# single_board_voice_changer.net
KiCad netlist of a schematic drawn in EAGLE
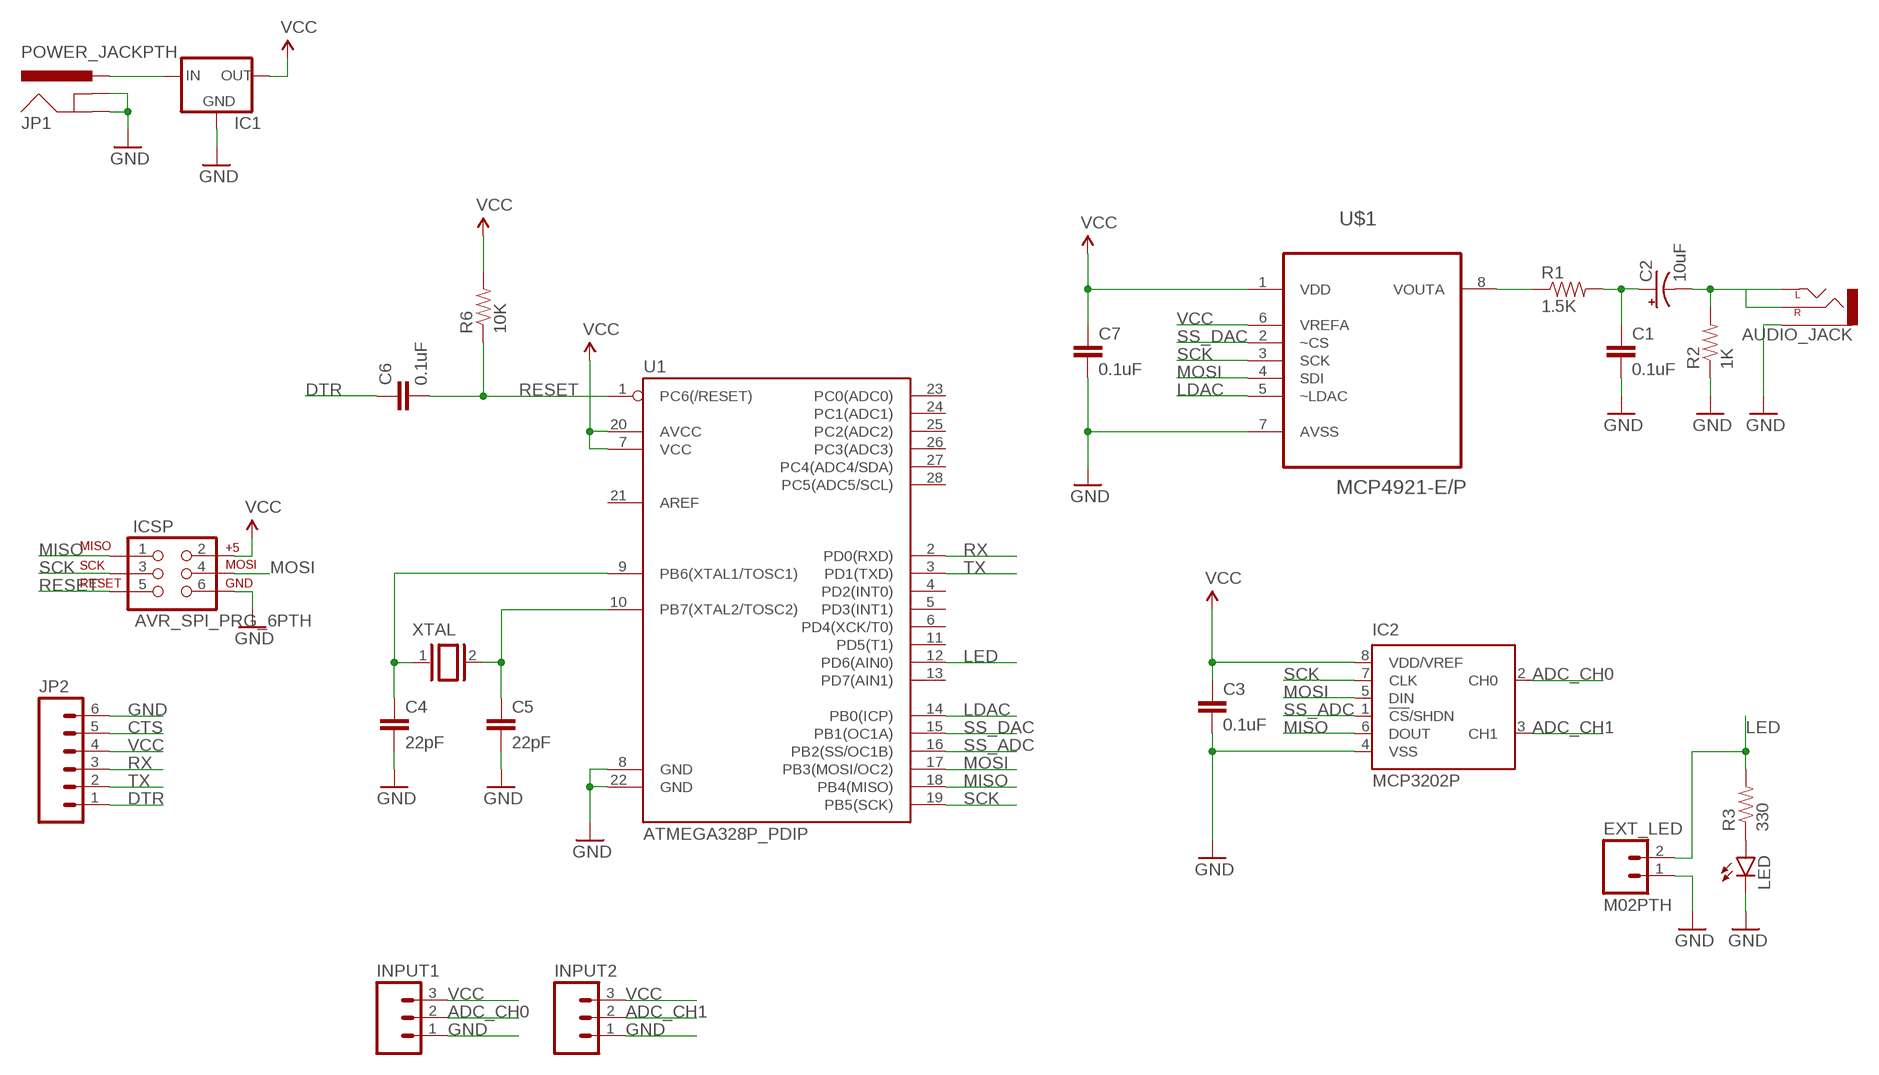
[diagram p0: schematic, sheet 1]

(export (version "E")
  (design (tool "Eeschema 10.0.6"))
  (components
    (comp (ref "AUDIO_JACK")
      (value "AUDIO-JACKPTH")
      (footprint "eagle-import:AUDIO-JACK")
      (libsource (lib "eagle-import") (part "AUDIO-JACKPTH"))
    )
    (comp (ref "C1")
      (value "0.1uF")
      (footprint "eagle-import:CAP-PTH-SMALL")
      (libsource (lib "eagle-import") (part "SparkFun-Passives_CAPPTH"))
    )
    (comp (ref "C2")
      (value "10uF")
      (footprint "eagle-import:CPOL-RADIAL-10UF-25V")
      (libsource (lib "eagle-import") (part "CAP_POLPTH2"))
    )
    (comp (ref "C3")
      (value "0.1uF")
      (footprint "eagle-import:CAP-PTH-SMALL")
      (libsource (lib "eagle-import") (part "SparkFun-Passives_CAPPTH"))
    )
    (comp (ref "C4")
      (value "22pF")
      (footprint "eagle-import:CAP-PTH-SMALL")
      (libsource (lib "eagle-import") (part "SparkFun-Passives_CAPPTH"))
    )
    (comp (ref "C5")
      (value "22pF")
      (footprint "eagle-import:CAP-PTH-SMALL")
      (libsource (lib "eagle-import") (part "SparkFun-Passives_CAPPTH"))
    )
    (comp (ref "C6")
      (value "0.1uF")
      (footprint "eagle-import:CAP-PTH-SMALL")
      (libsource (lib "eagle-import") (part "CAPPTH"))
    )
    (comp (ref "C7")
      (value "0.1uF")
      (footprint "eagle-import:CAP-PTH-SMALL")
      (libsource (lib "eagle-import") (part "SparkFun-Passives_CAPPTH"))
    )
    (comp (ref "EXT_LED")
      (value "M02PTH")
      (footprint "eagle-import:1X02")
      (libsource (lib "eagle-import") (part "M02PTH"))
    )
    (comp (ref "IC1")
      (value "V_REG_78XXSIDE")
      (footprint "eagle-import:78XXL")
      (libsource (lib "eagle-import") (part "V_REG_78XXSIDE"))
    )
    (comp (ref "IC2")
      (value "MCP3202P")
      (footprint "eagle-import:DIL8")
      (fields (field (name "MF") "MICROCHIP") (field (name "MPN") "MCP3202-CI/P"))
      (libsource (lib "eagle-import") (part "MCP3202P"))
    )
    (comp (ref "ICSP")
      (value "AVR_SPI_PRG_6PTH")
      (footprint "eagle-import:2X3")
      (libsource (lib "eagle-import") (part "AVR_SPI_PRG_6PTH"))
    )
    (comp (ref "INPUT1")
      (value "M03PTH")
      (footprint "eagle-import:1X03")
      (libsource (lib "eagle-import") (part "M03PTH"))
    )
    (comp (ref "INPUT2")
      (value "M03PTH")
      (footprint "eagle-import:1X03")
      (libsource (lib "eagle-import") (part "M03PTH"))
    )
    (comp (ref "JP1")
      (value "POWER_JACKPTH")
      (footprint "eagle-import:POWER_JACK_PTH")
      (libsource (lib "eagle-import") (part "POWER_JACKPTH"))
    )
    (comp (ref "JP2")
      (value "M06SILK_FEMALE_PTH")
      (footprint "eagle-import:1X06")
      (libsource (lib "eagle-import") (part "M06SILK_FEMALE_PTH"))
    )
    (comp (ref "LED")
      (value "LED5MM")
      (footprint "eagle-import:LED5MM")
      (libsource (lib "eagle-import") (part "LED5MM"))
    )
    (comp (ref "R1")
      (value "1.5K")
      (footprint "eagle-import:AXIAL-0.4")
      (libsource (lib "eagle-import") (part "RESISTORPTH-1/4W"))
    )
    (comp (ref "R2")
      (value "1K")
      (footprint "eagle-import:AXIAL-0.4")
      (libsource (lib "eagle-import") (part "RESISTORPTH-1/4W"))
    )
    (comp (ref "R3")
      (value "330")
      (footprint "eagle-import:AXIAL-0.4")
      (libsource (lib "eagle-import") (part "RESISTORPTH-1/4W"))
    )
    (comp (ref "R6")
      (value "10K")
      (footprint "eagle-import:AXIAL-0.4")
      (libsource (lib "eagle-import") (part "RESISTORPTH-1/4W"))
    )
    (comp (ref "U$1")
      (value "MCP4921-E/P")
      (footprint "eagle-import:DIP254P762X432-8")
      (libsource (lib "eagle-import") (part "MCP4921-E/P"))
    )
    (comp (ref "U1")
      (value "ATMEGA328P_PDIP")
      (footprint "eagle-import:DIL28-3")
      (libsource (lib "eagle-import") (part "ATMEGA328P_PDIP"))
    )
    (comp (ref "XTAL")
      (value "XTAL/S")
      (footprint "eagle-import:QS")
      (libsource (lib "eagle-import") (part "XTAL/S"))
    )
  )
  (nets
    (net (code "1") (name "/ADC_CH0") (class "Default")
      (node (ref "IC2") (pin "2") (pinfunction "CH0_2") (pintype "input"))
      (node (ref "INPUT1") (pin "2") (pinfunction "2_2") (pintype "passive"))
    )
    (net (code "2") (name "/ADC_CH1") (class "Default")
      (node (ref "IC2") (pin "3") (pinfunction "CH1_3") (pintype "input"))
      (node (ref "INPUT2") (pin "2") (pinfunction "2_2") (pintype "passive"))
    )
    (net (code "3") (name "/CTS") (class "Default")
      (node (ref "JP2") (pin "5") (pinfunction "5_5") (pintype "passive"))
    )
    (net (code "4") (name "/DTR") (class "Default")
      (node (ref "C6") (pin "1") (pinfunction "1_1") (pintype "passive"))
      (node (ref "JP2") (pin "1") (pinfunction "1_1") (pintype "passive"))
    )
    (net (code "5") (name "/LDAC") (class "Default")
      (node (ref "U$1") (pin "5") (pinfunction "~{LDAC}_5") (pintype "input"))
      (node (ref "U1") (pin "14") (pinfunction "PB0(ICP)_14") (pintype "bidirectional"))
    )
    (net (code "6") (name "/LED") (class "Default")
      (node (ref "EXT_LED") (pin "2") (pinfunction "2_2") (pintype "passive"))
      (node (ref "R3") (pin "P$2") (pinfunction "2_P$2") (pintype "passive"))
      (node (ref "U1") (pin "12") (pinfunction "PD6(AIN0)_12") (pintype "bidirectional"))
    )
    (net (code "7") (name "/MISO") (class "Default")
      (node (ref "IC2") (pin "6") (pinfunction "DOUT_6") (pintype "input"))
      (node (ref "ICSP") (pin "1") (pinfunction "1_1") (pintype "passive"))
      (node (ref "U1") (pin "18") (pinfunction "PB4(MISO)_18") (pintype "bidirectional"))
    )
    (net (code "8") (name "/MOSI") (class "Default")
      (node (ref "IC2") (pin "5") (pinfunction "DIN_5") (pintype "input"))
      (node (ref "ICSP") (pin "4") (pinfunction "4_4") (pintype "passive"))
      (node (ref "U$1") (pin "4") (pinfunction "SDI_4") (pintype "input"))
      (node (ref "U1") (pin "17") (pinfunction "PB3(MOSI/OC2)_17") (pintype "bidirectional"))
    )
    (net (code "9") (name "/RESET") (class "Default")
      (node (ref "C6") (pin "2") (pinfunction "2_2") (pintype "passive"))
      (node (ref "ICSP") (pin "5") (pinfunction "5_5") (pintype "passive"))
      (node (ref "R6") (pin "P$1") (pinfunction "1_P$1") (pintype "passive"))
      (node (ref "U1") (pin "1") (pinfunction "PC6(/RESET)_1") (pintype "bidirectional"))
    )
    (net (code "10") (name "/RX") (class "Default")
      (node (ref "JP2") (pin "3") (pinfunction "3_3") (pintype "passive"))
      (node (ref "U1") (pin "2") (pinfunction "PD0(RXD)_2") (pintype "bidirectional"))
    )
    (net (code "11") (name "/SCK") (class "Default")
      (node (ref "IC2") (pin "7") (pinfunction "CLK_7") (pintype "input"))
      (node (ref "ICSP") (pin "3") (pinfunction "3_3") (pintype "passive"))
      (node (ref "U$1") (pin "3") (pinfunction "SCK_3") (pintype "input"))
      (node (ref "U1") (pin "19") (pinfunction "PB5(SCK)_19") (pintype "bidirectional"))
    )
    (net (code "12") (name "/SS_ADC") (class "Default")
      (node (ref "IC2") (pin "1") (pinfunction "~{CS}/SHDN_1") (pintype "input"))
      (node (ref "U1") (pin "16") (pinfunction "PB2(SS/OC1B)_16") (pintype "bidirectional"))
    )
    (net (code "13") (name "/SS_DAC") (class "Default")
      (node (ref "U$1") (pin "2") (pinfunction "~{CS}_2") (pintype "input"))
      (node (ref "U1") (pin "15") (pinfunction "PB1(OC1A)_15") (pintype "bidirectional"))
    )
    (net (code "14") (name "/TX") (class "Default")
      (node (ref "JP2") (pin "2") (pinfunction "2_2") (pintype "passive"))
      (node (ref "U1") (pin "3") (pinfunction "PD1(TXD)_3") (pintype "bidirectional"))
    )
    (net (code "15") (name "GND") (class "Default")
      (node (ref "AUDIO_JACK") (pin "SLEEVE") (pinfunction "SLEEVE_SLEEVE") (pintype "bidirectional"))
      (node (ref "C1") (pin "2") (pinfunction "2_2") (pintype "passive"))
      (node (ref "C3") (pin "2") (pinfunction "2_2") (pintype "passive"))
      (node (ref "C4") (pin "2") (pinfunction "2_2") (pintype "passive"))
      (node (ref "C5") (pin "2") (pinfunction "2_2") (pintype "passive"))
      (node (ref "C7") (pin "2") (pinfunction "2_2") (pintype "passive"))
      (node (ref "EXT_LED") (pin "1") (pinfunction "1_1") (pintype "passive"))
      (node (ref "IC1") (pin "GND") (pinfunction "GND_GND") (pintype "input"))
      (node (ref "IC2") (pin "4") (pinfunction "VSS_4") (pintype "input"))
      (node (ref "ICSP") (pin "6") (pinfunction "6_6") (pintype "passive"))
      (node (ref "INPUT1") (pin "1") (pinfunction "1_1") (pintype "passive"))
      (node (ref "INPUT2") (pin "1") (pinfunction "1_1") (pintype "passive"))
      (node (ref "JP1") (pin "GND") (pinfunction "GND_GND") (pintype "bidirectional"))
      (node (ref "JP1") (pin "GNDBREAK") (pinfunction "GNDBREAK_GNDBREAK") (pintype "bidirectional"))
      (node (ref "JP2") (pin "6") (pinfunction "6_6") (pintype "passive"))
      (node (ref "LED") (pin "K") (pinfunction "C_K") (pintype "passive"))
      (node (ref "R2") (pin "P$1") (pinfunction "1_P$1") (pintype "passive"))
      (node (ref "U$1") (pin "7") (pinfunction "AVSS_7") (pintype "passive"))
      (node (ref "U1") (pin "22") (pinfunction "GND_22") (pintype "bidirectional"))
      (node (ref "U1") (pin "8") (pinfunction "GND_8") (pintype "bidirectional"))
    )
    (net (code "16") (name "Net-(AUDIO_JACK-LEFT)") (class "Default")
      (node (ref "AUDIO_JACK") (pin "RING") (pinfunction "RIGHT_RING") (pintype "bidirectional"))
      (node (ref "AUDIO_JACK") (pin "TIP") (pinfunction "LEFT_TIP") (pintype "bidirectional"))
      (node (ref "C2") (pin "2") (pinfunction "-_2") (pintype "passive"))
      (node (ref "R2") (pin "P$2") (pinfunction "2_P$2") (pintype "passive"))
    )
    (net (code "17") (name "Net-(C2-+)") (class "Default")
      (node (ref "C1") (pin "1") (pinfunction "1_1") (pintype "passive"))
      (node (ref "C2") (pin "1") (pinfunction "+_1") (pintype "passive"))
      (node (ref "R1") (pin "P$2") (pinfunction "2_P$2") (pintype "passive"))
    )
    (net (code "18") (name "Net-(IC1-PadIN)") (class "Default")
      (node (ref "IC1") (pin "IN") (pinfunction "IN_IN") (pintype "input"))
      (node (ref "JP1") (pin "PWR") (pinfunction "PWR_PWR") (pintype "bidirectional"))
    )
    (net (code "19") (name "Net-(R1-1)") (class "Default")
      (node (ref "R1") (pin "P$1") (pinfunction "1_P$1") (pintype "passive"))
      (node (ref "U$1") (pin "8") (pinfunction "VOUTA_8") (pintype "output"))
    )
    (net (code "20") (name "Net-(R3-1)") (class "Default")
      (node (ref "LED") (pin "A") (pinfunction "A_A") (pintype "passive"))
      (node (ref "R3") (pin "P$1") (pinfunction "1_P$1") (pintype "passive"))
    )
    (net (code "21") (name "Net-(U1-PB6(XTAL1{slash}TOSC1))") (class "Default")
      (node (ref "C4") (pin "1") (pinfunction "1_1") (pintype "passive"))
      (node (ref "U1") (pin "9") (pinfunction "PB6(XTAL1/TOSC1)_9") (pintype "bidirectional"))
      (node (ref "XTAL") (pin "1") (pinfunction "1_1") (pintype "passive"))
    )
    (net (code "22") (name "Net-(U1-PB7(XTAL2{slash}TOSC2))") (class "Default")
      (node (ref "C5") (pin "1") (pinfunction "1_1") (pintype "passive"))
      (node (ref "U1") (pin "10") (pinfunction "PB7(XTAL2/TOSC2)_10") (pintype "bidirectional"))
      (node (ref "XTAL") (pin "2") (pinfunction "2_2") (pintype "passive"))
    )
    (net (code "23") (name "VCC") (class "Default")
      (node (ref "C3") (pin "1") (pinfunction "1_1") (pintype "passive"))
      (node (ref "C7") (pin "1") (pinfunction "1_1") (pintype "passive"))
      (node (ref "IC1") (pin "OUT") (pinfunction "OUT_OUT") (pintype "output"))
      (node (ref "IC2") (pin "8") (pinfunction "VDD/VREF_8") (pintype "input"))
      (node (ref "ICSP") (pin "2") (pinfunction "2_2") (pintype "passive"))
      (node (ref "INPUT1") (pin "3") (pinfunction "3_3") (pintype "passive"))
      (node (ref "INPUT2") (pin "3") (pinfunction "3_3") (pintype "passive"))
      (node (ref "JP2") (pin "4") (pinfunction "4_4") (pintype "passive"))
      (node (ref "R6") (pin "P$2") (pinfunction "2_P$2") (pintype "passive"))
      (node (ref "U$1") (pin "1") (pinfunction "VDD_1") (pintype "power_in"))
      (node (ref "U$1") (pin "6") (pinfunction "VREFA_6") (pintype "input"))
      (node (ref "U1") (pin "20") (pinfunction "AVCC_20") (pintype "bidirectional"))
      (node (ref "U1") (pin "7") (pinfunction "VCC_7") (pintype "bidirectional"))
    )
    (net (code "24") (name "unconnected-(U1-AREF-Pad21)") (class "Default")
      (node (ref "U1") (pin "21") (pinfunction "AREF_21") (pintype "bidirectional"))
    )
    (net (code "25") (name "unconnected-(U1-PC0(ADC0)-Pad23)") (class "Default")
      (node (ref "U1") (pin "23") (pinfunction "PC0(ADC0)_23") (pintype "bidirectional"))
    )
    (net (code "26") (name "unconnected-(U1-PC1(ADC1)-Pad24)") (class "Default")
      (node (ref "U1") (pin "24") (pinfunction "PC1(ADC1)_24") (pintype "bidirectional"))
    )
    (net (code "27") (name "unconnected-(U1-PC2(ADC2)-Pad25)") (class "Default")
      (node (ref "U1") (pin "25") (pinfunction "PC2(ADC2)_25") (pintype "bidirectional"))
    )
    (net (code "28") (name "unconnected-(U1-PC3(ADC3)-Pad26)") (class "Default")
      (node (ref "U1") (pin "26") (pinfunction "PC3(ADC3)_26") (pintype "bidirectional"))
    )
    (net (code "29") (name "unconnected-(U1-PC4(ADC4{slash}SDA)-Pad27)") (class "Default")
      (node (ref "U1") (pin "27") (pinfunction "PC4(ADC4/SDA)_27") (pintype "bidirectional"))
    )
    (net (code "30") (name "unconnected-(U1-PC5(ADC5{slash}SCL)-Pad28)") (class "Default")
      (node (ref "U1") (pin "28") (pinfunction "PC5(ADC5/SCL)_28") (pintype "bidirectional"))
    )
    (net (code "31") (name "unconnected-(U1-PD2(INT0)-Pad4)") (class "Default")
      (node (ref "U1") (pin "4") (pinfunction "PD2(INT0)_4") (pintype "bidirectional"))
    )
    (net (code "32") (name "unconnected-(U1-PD3(INT1)-Pad5)") (class "Default")
      (node (ref "U1") (pin "5") (pinfunction "PD3(INT1)_5") (pintype "bidirectional"))
    )
    (net (code "33") (name "unconnected-(U1-PD4(XCK{slash}T0)-Pad6)") (class "Default")
      (node (ref "U1") (pin "6") (pinfunction "PD4(XCK/T0)_6") (pintype "bidirectional"))
    )
    (net (code "34") (name "unconnected-(U1-PD5(T1)-Pad11)") (class "Default")
      (node (ref "U1") (pin "11") (pinfunction "PD5(T1)_11") (pintype "bidirectional"))
    )
    (net (code "35") (name "unconnected-(U1-PD7(AIN1)-Pad13)") (class "Default")
      (node (ref "U1") (pin "13") (pinfunction "PD7(AIN1)_13") (pintype "bidirectional"))
    )
  )
)
